# pc_max86150_breakout_qwiic2part_part1.net
KiCad netlist of a schematic drawn in EAGLE
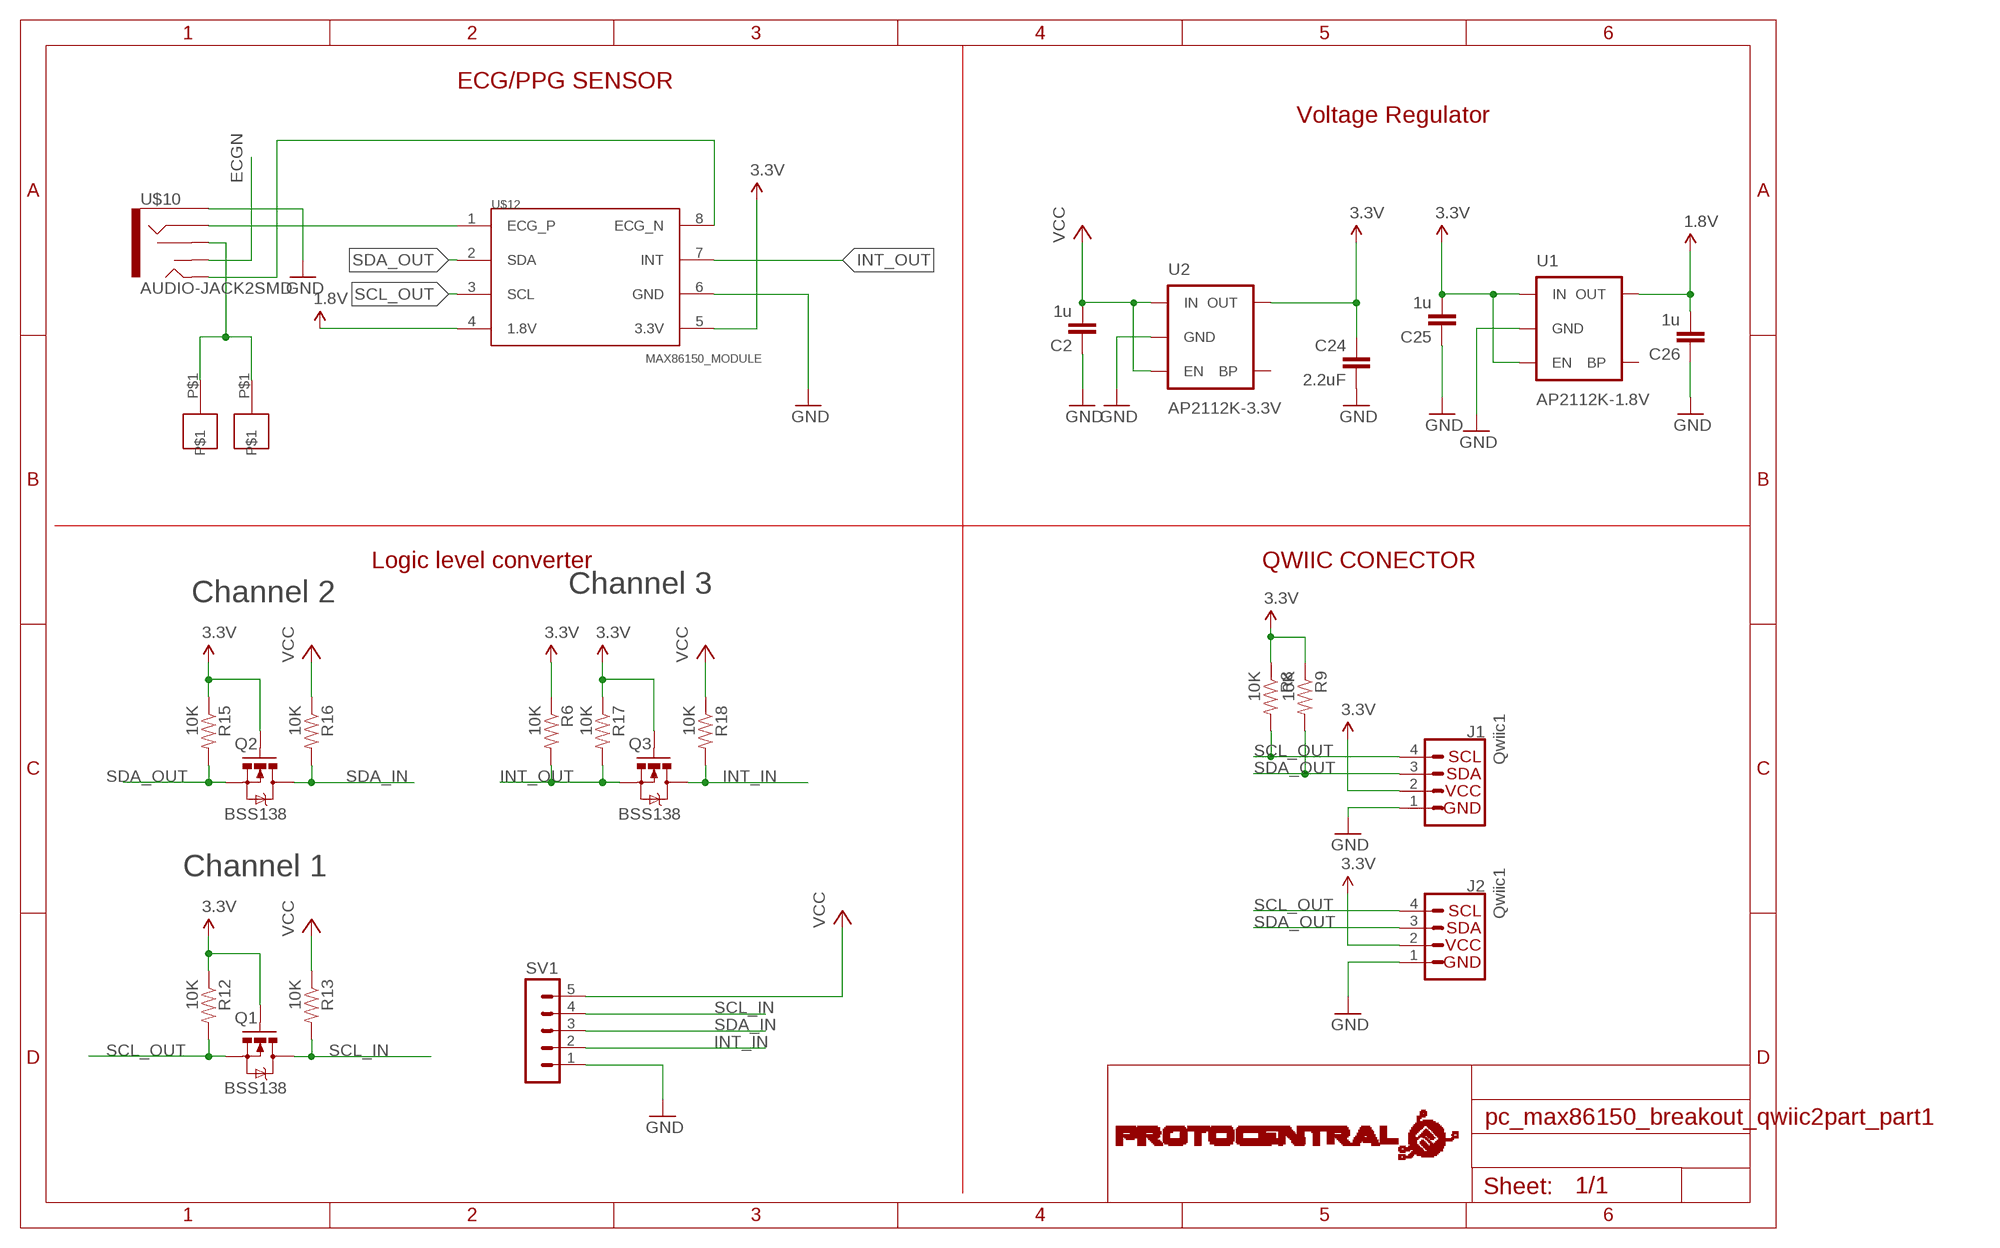
[diagram p0: schematic, sheet 1]

(export (version "E")
  (design (tool "Eeschema 10.0.6"))
  (components
    (comp (ref "C2")
      (value "1u")
      (footprint "eagle-import:C0402")
      (libsource (lib "eagle-import") (part "C-EUC0402"))
    )
    (comp (ref "C24")
      (value "2.2uF")
      (footprint "eagle-import:C0402")
      (libsource (lib "eagle-import") (part "C-EUC0402"))
    )
    (comp (ref "C25")
      (value "1u")
      (footprint "eagle-import:C0402")
      (libsource (lib "eagle-import") (part "C-EUC0402"))
    )
    (comp (ref "C26")
      (value "1u")
      (footprint "eagle-import:C0402")
      (libsource (lib "eagle-import") (part "C-EUC0402"))
    )
    (comp (ref "J1")
      (value "Qwiic1")
      (footprint "eagle-import:1X04_1MM_RA")
      (libsource (lib "eagle-import") (part "QWIIC_CONNECTORJS-1MM"))
    )
    (comp (ref "J2")
      (value "Qwiic1")
      (footprint "eagle-import:1X04_1MM_RA")
      (libsource (lib "eagle-import") (part "QWIIC_CONNECTORJS-1MM"))
    )
    (comp (ref "Q1")
      (value "BSS138")
      (footprint "eagle-import:SOT23-3")
      (libsource (lib "eagle-import") (part "MOSFET-NCHANNELSMD"))
    )
    (comp (ref "Q2")
      (value "BSS138")
      (footprint "eagle-import:SOT23-3")
      (libsource (lib "eagle-import") (part "MOSFET-NCHANNELSMD"))
    )
    (comp (ref "Q3")
      (value "BSS138")
      (footprint "eagle-import:SOT23-3")
      (libsource (lib "eagle-import") (part "MOSFET-NCHANNELSMD"))
    )
    (comp (ref "R6")
      (value "10K")
      (footprint "eagle-import:0402-RES")
      (libsource (lib "eagle-import") (part "RESISTOR0402-RES"))
    )
    (comp (ref "R8")
      (value "10K")
      (footprint "eagle-import:0402-RES")
      (libsource (lib "eagle-import") (part "RESISTOR0402-RES"))
    )
    (comp (ref "R9")
      (value "10K")
      (footprint "eagle-import:0402-RES")
      (libsource (lib "eagle-import") (part "RESISTOR0402-RES"))
    )
    (comp (ref "R12")
      (value "10K")
      (footprint "eagle-import:0402-RES")
      (libsource (lib "eagle-import") (part "RESISTOR0402-RES"))
    )
    (comp (ref "R13")
      (value "10K")
      (footprint "eagle-import:0402-RES")
      (libsource (lib "eagle-import") (part "RESISTOR0402-RES"))
    )
    (comp (ref "R15")
      (value "10K")
      (footprint "eagle-import:0402-RES")
      (libsource (lib "eagle-import") (part "RESISTOR0402-RES"))
    )
    (comp (ref "R16")
      (value "10K")
      (footprint "eagle-import:0402-RES")
      (libsource (lib "eagle-import") (part "RESISTOR0402-RES"))
    )
    (comp (ref "R17")
      (value "10K")
      (footprint "eagle-import:0402-RES")
      (libsource (lib "eagle-import") (part "RESISTOR0402-RES"))
    )
    (comp (ref "R18")
      (value "10K")
      (footprint "eagle-import:0402-RES")
      (libsource (lib "eagle-import") (part "RESISTOR0402-RES"))
    )
    (comp (ref "SV1")
      (value "MA05-1")
      (footprint "eagle-import:MA05-1")
      (libsource (lib "eagle-import") (part "MA05-1"))
    )
    (comp (ref "U$3")
      (value "PROTY_LOGO_WITH_TEXT")
      (footprint "eagle-import:PROTY_WITH_TEXT")
      (libsource (lib "eagle-import") (part "PROTY_LOGO_WITH_TEXT"))
    )
    (comp (ref "U$4")
      (value "ECG_PAD")
      (footprint "eagle-import:ECG_PAD1")
      (libsource (lib "eagle-import") (part "ECG_PAD"))
    )
    (comp (ref "U$10")
      (value "AUDIO-JACK2SMD")
      (footprint "eagle-import:AUDIO-JACK-3.5MM-SMD")
      (libsource (lib "eagle-import") (part "AUDIO-JACK2SMD"))
    )
    (comp (ref "U$12")
      (value "MAX86150_MODULE")
      (footprint "eagle-import:MAX86150_MODULE")
      (libsource (lib "eagle-import") (part "MAX86150_MODULE"))
    )
    (comp (ref "U$13")
      (value "ECG_PAD")
      (footprint "eagle-import:ECG_PAD1")
      (libsource (lib "eagle-import") (part "ECG_PAD"))
    )
    (comp (ref "U1")
      (value "AP2112K-1.8V")
      (footprint "eagle-import:SOT23-5")
      (libsource (lib "eagle-import") (part "V_REG_LDOSMD"))
    )
    (comp (ref "U2")
      (value "AP2112K-3.3V")
      (footprint "eagle-import:SOT23-5")
      (libsource (lib "eagle-import") (part "V_REG_LDOSMD"))
    )
  )
  (nets
    (net (code "1") (name "/ECGN") (class "Default")
      (node (ref "U$10") (pin "TSH") (pinfunction "TSH_TSH") (pintype "bidirectional"))
    )
    (net (code "2") (name "/INT_IN") (class "Default")
      (node (ref "Q3") (pin "3") (pinfunction "D_3") (pintype "passive"))
      (node (ref "R18") (pin "2") (pinfunction "2_2") (pintype "passive"))
      (node (ref "SV1") (pin "2") (pinfunction "2_2") (pintype "passive"))
    )
    (net (code "3") (name "/SCL_IN") (class "Default")
      (node (ref "Q1") (pin "3") (pinfunction "D_3") (pintype "passive"))
      (node (ref "R13") (pin "2") (pinfunction "2_2") (pintype "passive"))
      (node (ref "SV1") (pin "4") (pinfunction "4_4") (pintype "passive"))
    )
    (net (code "4") (name "/SDA_IN") (class "Default")
      (node (ref "Q2") (pin "3") (pinfunction "D_3") (pintype "passive"))
      (node (ref "R16") (pin "2") (pinfunction "2_2") (pintype "passive"))
      (node (ref "SV1") (pin "3") (pinfunction "3_3") (pintype "passive"))
    )
    (net (code "5") (name "1.8V") (class "Default")
      (node (ref "C26") (pin "2") (pinfunction "2_2") (pintype "passive"))
      (node (ref "U$12") (pin "4") (pinfunction "1.8V_4") (pintype "bidirectional"))
      (node (ref "U1") (pin "5") (pinfunction "OUT_5") (pintype "passive"))
    )
    (net (code "6") (name "3.3V") (class "Default")
      (node (ref "C24") (pin "1") (pinfunction "1_1") (pintype "passive"))
      (node (ref "C25") (pin "2") (pinfunction "2_2") (pintype "passive"))
      (node (ref "J1") (pin "2") (pinfunction "2_2") (pintype "power_in"))
      (node (ref "J2") (pin "2") (pinfunction "2_2") (pintype "power_in"))
      (node (ref "Q1") (pin "1") (pinfunction "G_1") (pintype "passive"))
      (node (ref "Q2") (pin "1") (pinfunction "G_1") (pintype "passive"))
      (node (ref "Q3") (pin "1") (pinfunction "G_1") (pintype "passive"))
      (node (ref "R12") (pin "1") (pinfunction "1_1") (pintype "passive"))
      (node (ref "R15") (pin "1") (pinfunction "1_1") (pintype "passive"))
      (node (ref "R17") (pin "1") (pinfunction "1_1") (pintype "passive"))
      (node (ref "R6") (pin "1") (pinfunction "1_1") (pintype "passive"))
      (node (ref "R8") (pin "1") (pinfunction "1_1") (pintype "passive"))
      (node (ref "R9") (pin "1") (pinfunction "1_1") (pintype "passive"))
      (node (ref "U$12") (pin "5") (pinfunction "3.3V_5") (pintype "bidirectional"))
      (node (ref "U1") (pin "1") (pinfunction "IN_1") (pintype "input"))
      (node (ref "U1") (pin "3") (pinfunction "EN_3") (pintype "input"))
      (node (ref "U2") (pin "5") (pinfunction "OUT_5") (pintype "passive"))
    )
    (net (code "7") (name "GND") (class "Default")
      (node (ref "C2") (pin "1") (pinfunction "1_1") (pintype "passive"))
      (node (ref "C24") (pin "2") (pinfunction "2_2") (pintype "passive"))
      (node (ref "C25") (pin "1") (pinfunction "1_1") (pintype "passive"))
      (node (ref "C26") (pin "1") (pinfunction "1_1") (pintype "passive"))
      (node (ref "J1") (pin "1") (pinfunction "1_1") (pintype "power_in"))
      (node (ref "J2") (pin "1") (pinfunction "1_1") (pintype "power_in"))
      (node (ref "SV1") (pin "1") (pinfunction "1_1") (pintype "passive"))
      (node (ref "U$10") (pin "SLEEVE") (pinfunction "SLEEVE_SLEEVE") (pintype "bidirectional"))
      (node (ref "U$12") (pin "6") (pinfunction "GND_6") (pintype "bidirectional"))
      (node (ref "U1") (pin "2") (pinfunction "GND_2") (pintype "input"))
      (node (ref "U2") (pin "2") (pinfunction "GND_2") (pintype "input"))
    )
    (net (code "8") (name "INT_OUT") (class "Default")
      (node (ref "Q3") (pin "2") (pinfunction "S_2") (pintype "passive"))
      (node (ref "R17") (pin "2") (pinfunction "2_2") (pintype "passive"))
      (node (ref "R6") (pin "2") (pinfunction "2_2") (pintype "passive"))
      (node (ref "U$12") (pin "7") (pinfunction "INT_7") (pintype "bidirectional"))
    )
    (net (code "9") (name "Net-(U$10-PadRSH)") (class "Default")
      (node (ref "U$10") (pin "RSH") (pinfunction "RSH_RSH") (pintype "bidirectional"))
      (node (ref "U$13") (pin "P$1") (pinfunction "P$1_P$1") (pintype "bidirectional"))
      (node (ref "U$4") (pin "P$1") (pinfunction "P$1_P$1") (pintype "bidirectional"))
    )
    (net (code "10") (name "Net-(U$12-ECG_N)") (class "Default")
      (node (ref "U$10") (pin "TIP") (pinfunction "TIP_TIP") (pintype "bidirectional"))
      (node (ref "U$12") (pin "8") (pinfunction "ECG_N_8") (pintype "bidirectional"))
    )
    (net (code "11") (name "Net-(U$12-ECG_P)") (class "Default")
      (node (ref "U$10") (pin "RING") (pinfunction "RING_RING") (pintype "bidirectional"))
      (node (ref "U$12") (pin "1") (pinfunction "ECG_P_1") (pintype "bidirectional"))
    )
    (net (code "12") (name "SCL_OUT") (class "Default")
      (node (ref "J1") (pin "4") (pinfunction "4_4") (pintype "passive"))
      (node (ref "J2") (pin "4") (pinfunction "4_4") (pintype "passive"))
      (node (ref "Q1") (pin "2") (pinfunction "S_2") (pintype "passive"))
      (node (ref "R12") (pin "2") (pinfunction "2_2") (pintype "passive"))
      (node (ref "R8") (pin "2") (pinfunction "2_2") (pintype "passive"))
      (node (ref "U$12") (pin "3") (pinfunction "SCL_3") (pintype "bidirectional"))
    )
    (net (code "13") (name "SDA_OUT") (class "Default")
      (node (ref "J1") (pin "3") (pinfunction "3_3") (pintype "passive"))
      (node (ref "J2") (pin "3") (pinfunction "3_3") (pintype "passive"))
      (node (ref "Q2") (pin "2") (pinfunction "S_2") (pintype "passive"))
      (node (ref "R15") (pin "2") (pinfunction "2_2") (pintype "passive"))
      (node (ref "R9") (pin "2") (pinfunction "2_2") (pintype "passive"))
      (node (ref "U$12") (pin "2") (pinfunction "SDA_2") (pintype "bidirectional"))
    )
    (net (code "14") (name "VCC") (class "Default")
      (node (ref "C2") (pin "2") (pinfunction "2_2") (pintype "passive"))
      (node (ref "R13") (pin "1") (pinfunction "1_1") (pintype "passive"))
      (node (ref "R16") (pin "1") (pinfunction "1_1") (pintype "passive"))
      (node (ref "R18") (pin "1") (pinfunction "1_1") (pintype "passive"))
      (node (ref "SV1") (pin "5") (pinfunction "5_5") (pintype "passive"))
      (node (ref "U2") (pin "1") (pinfunction "IN_1") (pintype "input"))
      (node (ref "U2") (pin "3") (pinfunction "EN_3") (pintype "input"))
    )
    (net (code "15") (name "unconnected-(U1-BP-Pad4)") (class "Default")
      (node (ref "U1") (pin "4") (pinfunction "BP_4") (pintype "input"))
    )
    (net (code "16") (name "unconnected-(U2-BP-Pad4)") (class "Default")
      (node (ref "U2") (pin "4") (pinfunction "BP_4") (pintype "input"))
    )
  )
)
